# Digispark_DIY.net
KiCad netlist of a schematic drawn in EasyEDA Pro
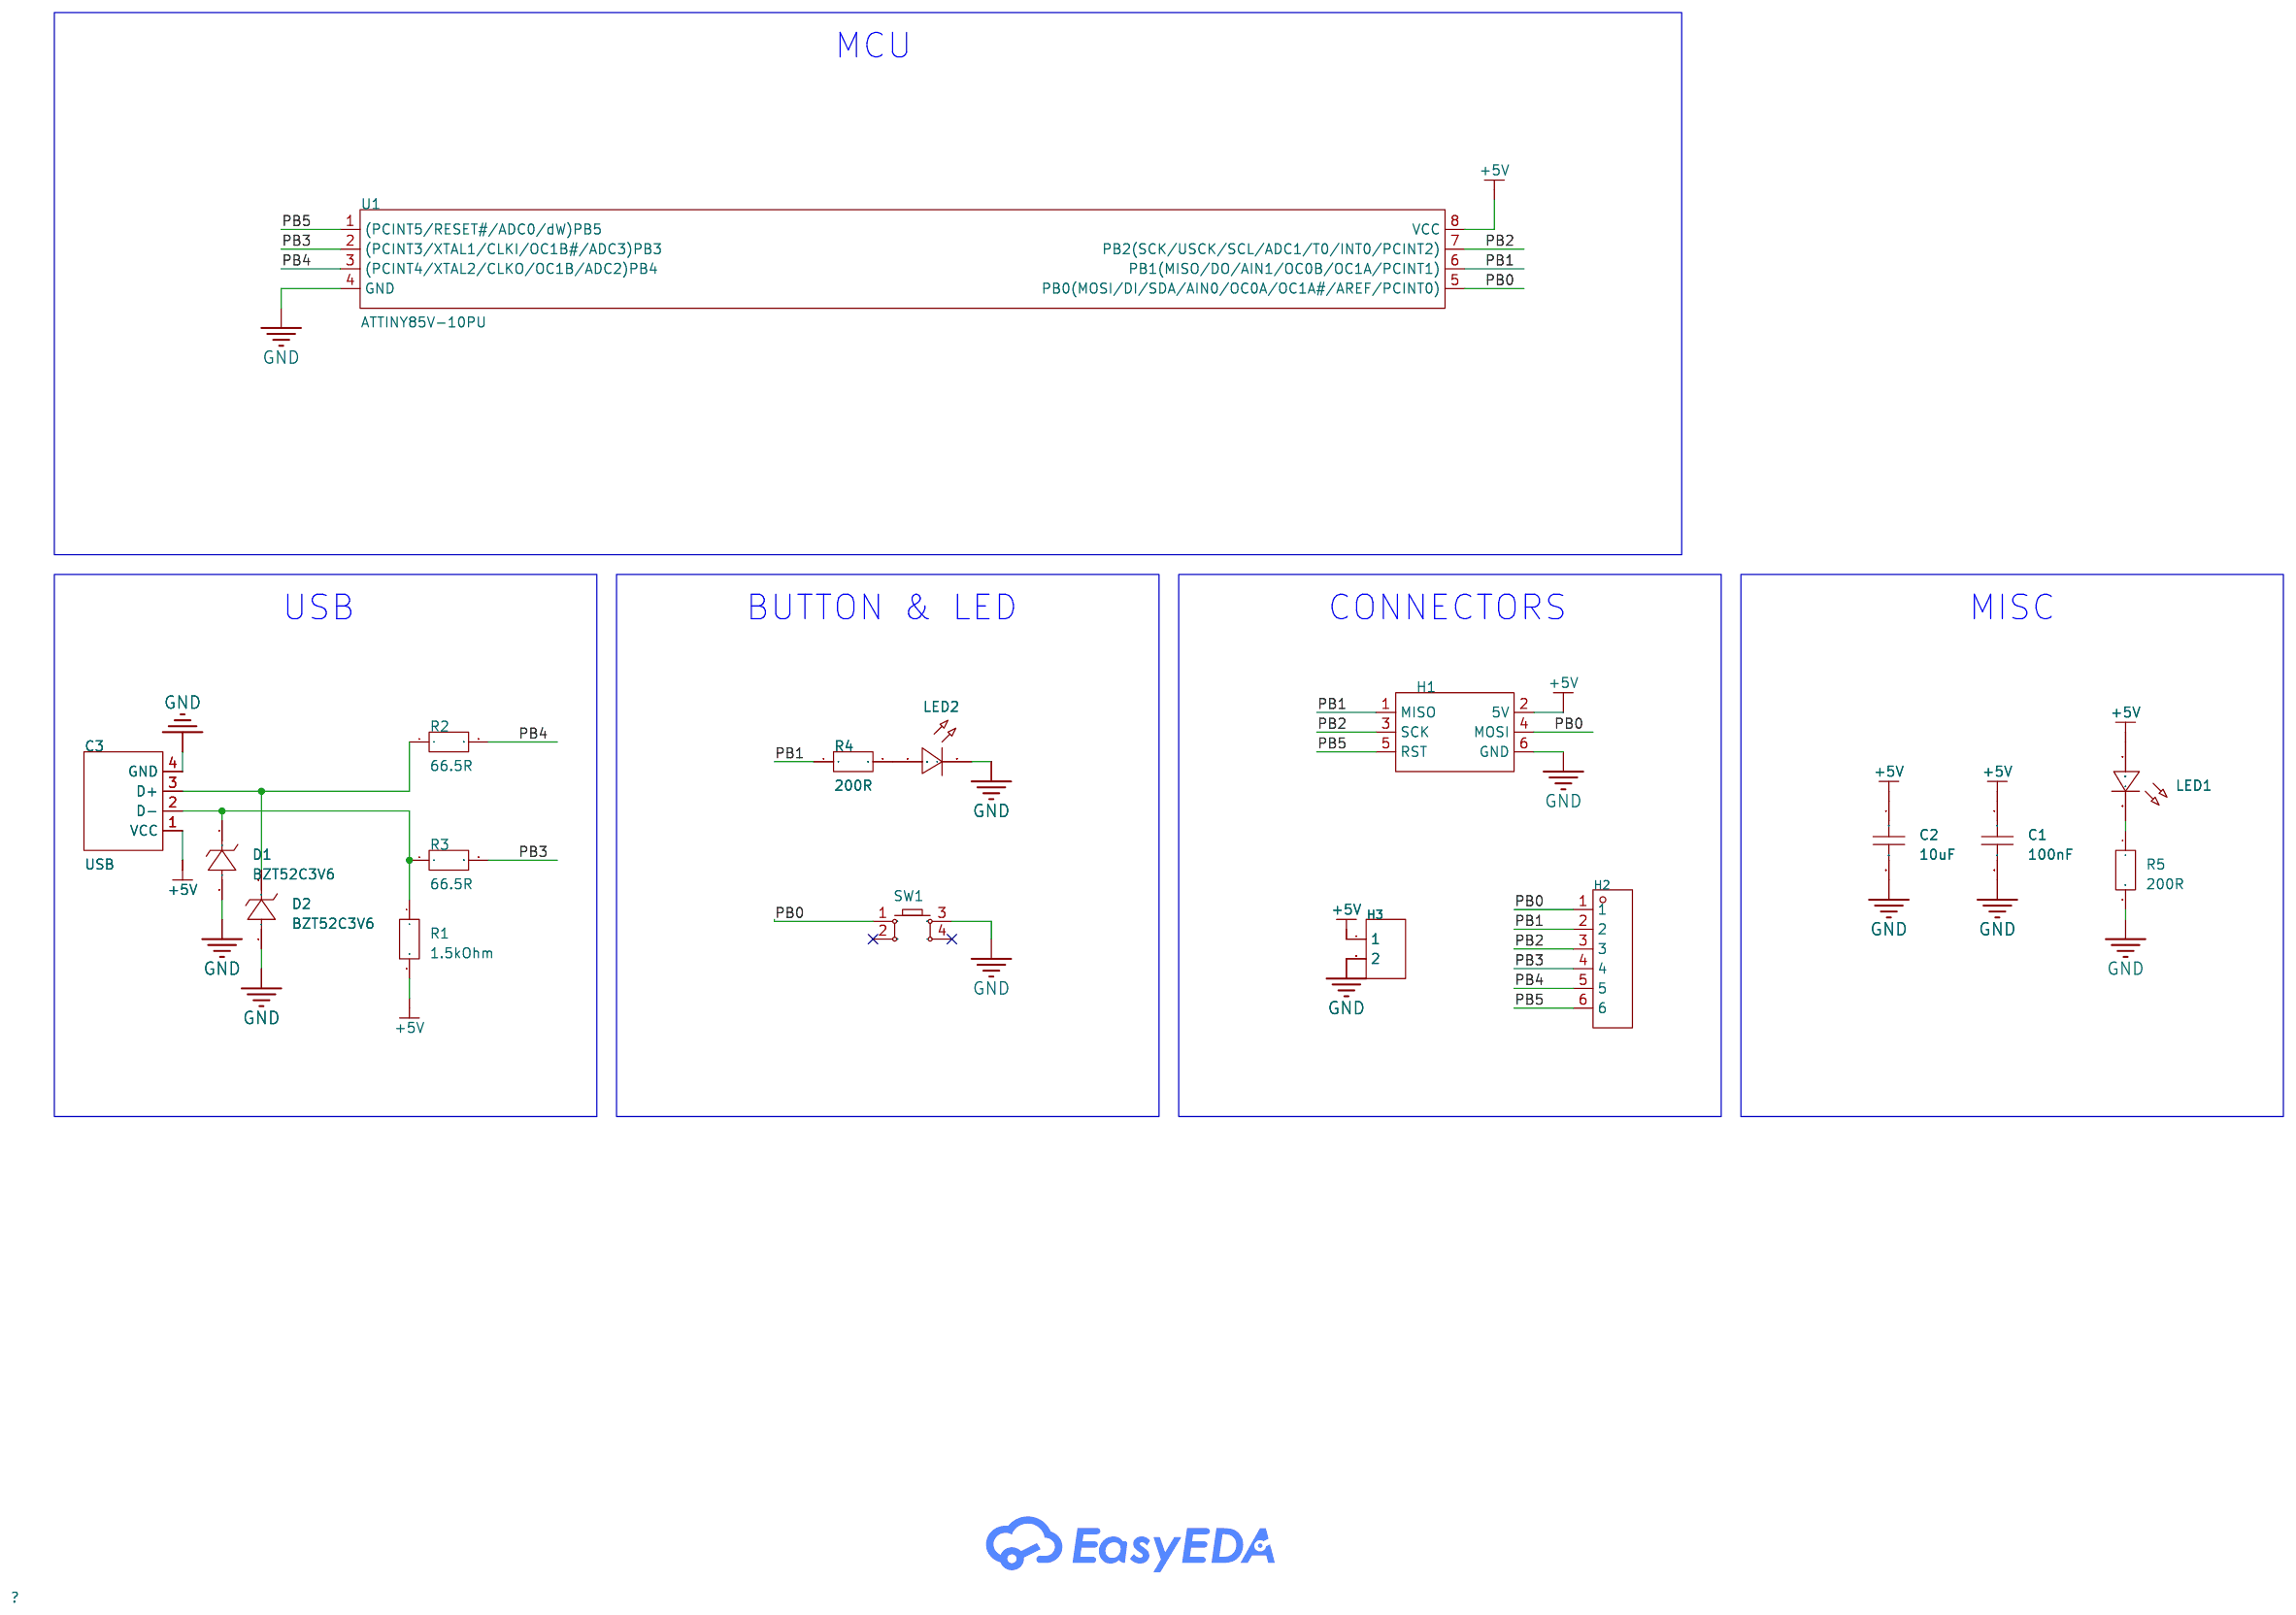
[diagram p0: schematic sheet]

(export (version "E")
  (design (tool "Eeschema 10.0.6"))
  (components
    (comp (ref "C1")
      (value "100nF")
      (footprint "easyedapro:C0805")
      (libsource (lib "easyedapro") (part "CAP"))
    )
    (comp (ref "C2")
      (value "10uF")
      (footprint "easyedapro:C0805")
      (libsource (lib "easyedapro") (part "CAP"))
    )
    (comp (ref "C3")
      (value "USB")
      (footprint "easyedapro:USB Type-C 4P")
      (libsource (lib "easyedapro") (part "USB Type-C 4P"))
    )
    (comp (ref "D1")
      (value "BZT52C3V6")
      (footprint "easyedapro:SOD-123_L2.7-W1.6-LS3.7-RD-1")
      (fields (field (name "Manufacturer") "FUXINSEMI(富芯森美)"))
      (libsource (lib "easyedapro") (part "BZT52C3V6_C908187"))
    )
    (comp (ref "D2")
      (value "BZT52C3V6")
      (footprint "easyedapro:SOD-123_L2.7-W1.6-LS3.7-RD-1")
      (fields (field (name "Manufacturer") "FUXINSEMI(富芯森美)"))
      (libsource (lib "easyedapro") (part "BZT52C3V6_C908187"))
    )
    (comp (ref "H1")
      (value "~")
      (footprint "easyedapro:HDR-TH_6P-P2.54-V-F-R2-C3-S2.54")
      (libsource (lib "easyedapro") (part "HDR-F-2.54_2x3"))
    )
    (comp (ref "H2")
      (value "~")
      (footprint "easyedapro:HDR-TH_6P-P2.54-V-F")
      (libsource (lib "easyedapro") (part "Header-Female-2.54_1x6"))
    )
    (comp (ref "H3")
      (value "~")
      (footprint "easyedapro:HDR-TH_2P-P2.54-V-F")
      (libsource (lib "easyedapro") (part "Header-Female-2.54_1x2"))
    )
    (comp (ref "LED1")
      (value "~")
      (footprint "easyedapro:LED-TH_BD3.0-P2.54-FD")
      (libsource (lib "easyedapro") (part "LED_TH-R"))
    )
    (comp (ref "LED2")
      (value "~")
      (footprint "easyedapro:LED-TH_BD3.8-P2.54-FD_BLUE")
      (libsource (lib "easyedapro") (part "LED_TH-B"))
    )
    (comp (ref "R1")
      (value "1.5kOhm")
      (footprint "easyedapro:R0805")
      (libsource (lib "easyedapro") (part "Resistor 0805"))
    )
    (comp (ref "R2")
      (value "66.5R")
      (footprint "easyedapro:R0805")
      (libsource (lib "easyedapro") (part "Resistor 0805"))
    )
    (comp (ref "R3")
      (value "66.5R")
      (footprint "easyedapro:R0805")
      (libsource (lib "easyedapro") (part "Resistor 0805"))
    )
    (comp (ref "R4")
      (value "200R")
      (footprint "easyedapro:R0805")
      (libsource (lib "easyedapro") (part "Resistor 0805"))
    )
    (comp (ref "R5")
      (value "200R")
      (footprint "easyedapro:R0805")
      (libsource (lib "easyedapro") (part "Resistor 0805"))
    )
    (comp (ref "SW1")
      (value "~")
      (footprint "easyedapro:KEY-TH_4P-L6.0-W6.0-P3.90-LS6.5")
      (libsource (lib "easyedapro") (part "轻触按键"))
    )
    (comp (ref "U1")
      (value "ATTINY85V-10PU")
      (footprint "easyedapro:PDIP-8_L9.6-W6.4-P2.54-LS7.6-BL")
      (fields (field (name "Manufacturer") "MICROCHIP(美国微芯)"))
      (libsource (lib "easyedapro") (part "ATTINY85V-10PU"))
    )
  )
  (nets
    (net (code "1") (name "+5V") (class "Default")
      (node (ref "C1") (pin "1") (pinfunction "1_1") (pintype "input"))
      (node (ref "C2") (pin "1") (pinfunction "1_1") (pintype "input"))
      (node (ref "C3") (pin "1") (pinfunction "VCC_1") (pintype "input"))
      (node (ref "H1") (pin "2") (pinfunction "5V_2") (pintype "input"))
      (node (ref "H3") (pin "1") (pinfunction "1_1") (pintype "input"))
      (node (ref "LED1") (pin "1") (pinfunction "C_1") (pintype "input"))
      (node (ref "R1") (pin "2") (pinfunction "2_2") (pintype "unspecified"))
      (node (ref "U1") (pin "8") (pinfunction "VCC_8") (pintype "unspecified"))
    )
    (net (code "2") (name "/PB0") (class "Default")
      (node (ref "H1") (pin "4") (pinfunction "MOSI_4") (pintype "input"))
      (node (ref "H2") (pin "1") (pinfunction "1_1") (pintype "input"))
      (node (ref "SW1") (pin "1") (pinfunction "1_1") (pintype "input"))
      (node (ref "U1") (pin "5") (pinfunction "PB0(MOSI/DI/SDA/AIN0/OC0A/OC1A#/AREF/PCINT0)_5") (pintype "unspecified"))
    )
    (net (code "3") (name "/PB1") (class "Default")
      (node (ref "H1") (pin "1") (pinfunction "MISO_1") (pintype "input"))
      (node (ref "H2") (pin "2") (pinfunction "2_2") (pintype "input"))
      (node (ref "R4") (pin "1") (pinfunction "1_1") (pintype "unspecified"))
      (node (ref "U1") (pin "6") (pinfunction "PB1(MISO/DO/AIN1/OC0B/OC1A/PCINT1)_6") (pintype "unspecified"))
    )
    (net (code "4") (name "/PB2") (class "Default")
      (node (ref "H1") (pin "3") (pinfunction "SCK_3") (pintype "input"))
      (node (ref "H2") (pin "3") (pinfunction "3_3") (pintype "input"))
      (node (ref "U1") (pin "7") (pinfunction "PB2(SCK/USCK/SCL/ADC1/T0/INT0/PCINT2)_7") (pintype "unspecified"))
    )
    (net (code "5") (name "/PB3") (class "Default")
      (node (ref "H2") (pin "4") (pinfunction "4_4") (pintype "input"))
      (node (ref "R3") (pin "2") (pinfunction "2_2") (pintype "unspecified"))
      (node (ref "U1") (pin "2") (pinfunction "(PCINT3/XTAL1/CLKI/OC1B#/ADC3)PB3_2") (pintype "unspecified"))
    )
    (net (code "6") (name "/PB4") (class "Default")
      (node (ref "H2") (pin "5") (pinfunction "5_5") (pintype "input"))
      (node (ref "R2") (pin "2") (pinfunction "2_2") (pintype "unspecified"))
      (node (ref "U1") (pin "3") (pinfunction "(PCINT4/XTAL2/CLKO/OC1B/ADC2)PB4_3") (pintype "unspecified"))
    )
    (net (code "7") (name "/PB5") (class "Default")
      (node (ref "H1") (pin "5") (pinfunction "RST_5") (pintype "input"))
      (node (ref "H2") (pin "6") (pinfunction "6_6") (pintype "input"))
      (node (ref "U1") (pin "1") (pinfunction "(PCINT5/RESET#/ADC0/dW)PB5_1") (pintype "unspecified"))
    )
    (net (code "8") (name "GND") (class "Default")
      (node (ref "C1") (pin "2") (pinfunction "2_2") (pintype "input"))
      (node (ref "C2") (pin "2") (pinfunction "2_2") (pintype "input"))
      (node (ref "C3") (pin "4") (pinfunction "GND_4") (pintype "input"))
      (node (ref "D1") (pin "2") (pinfunction "A_2") (pintype "unspecified"))
      (node (ref "D2") (pin "2") (pinfunction "A_2") (pintype "unspecified"))
      (node (ref "H1") (pin "6") (pinfunction "GND_6") (pintype "input"))
      (node (ref "H3") (pin "2") (pinfunction "2_2") (pintype "input"))
      (node (ref "LED2") (pin "2") (pinfunction "A_2") (pintype "input"))
      (node (ref "R5") (pin "2") (pinfunction "2_2") (pintype "unspecified"))
      (node (ref "SW1") (pin "3") (pinfunction "3_3") (pintype "input"))
      (node (ref "U1") (pin "4") (pinfunction "GND_4") (pintype "unspecified"))
    )
    (net (code "9") (name "Net-(C3-D+)") (class "Default")
      (node (ref "C3") (pin "3") (pinfunction "D+_3") (pintype "input"))
      (node (ref "D2") (pin "1") (pinfunction "K_1") (pintype "unspecified"))
      (node (ref "R2") (pin "1") (pinfunction "1_1") (pintype "unspecified"))
    )
    (net (code "10") (name "Net-(C3-D-)") (class "Default")
      (node (ref "C3") (pin "2") (pinfunction "D-_2") (pintype "input"))
      (node (ref "D1") (pin "1") (pinfunction "K_1") (pintype "unspecified"))
      (node (ref "R1") (pin "1") (pinfunction "1_1") (pintype "unspecified"))
      (node (ref "R3") (pin "1") (pinfunction "1_1") (pintype "unspecified"))
    )
    (net (code "11") (name "Net-(LED1-A)") (class "Default")
      (node (ref "LED1") (pin "2") (pinfunction "A_2") (pintype "input"))
      (node (ref "R5") (pin "1") (pinfunction "1_1") (pintype "unspecified"))
    )
    (net (code "12") (name "Net-(LED2-C)") (class "Default")
      (node (ref "LED2") (pin "1") (pinfunction "C_1") (pintype "input"))
      (node (ref "R4") (pin "2") (pinfunction "2_2") (pintype "unspecified"))
    )
    (net (code "13") (name "unconnected-(SW1-Pad2)") (class "Default")
      (node (ref "SW1") (pin "2") (pinfunction "2_2") (pintype "input+no_connect"))
    )
    (net (code "14") (name "unconnected-(SW1-Pad4)") (class "Default")
      (node (ref "SW1") (pin "4") (pinfunction "4_4") (pintype "input+no_connect"))
    )
  )
)
